# ControlDCMotors.net
KiCad netlist of a schematic drawn in EAGLE
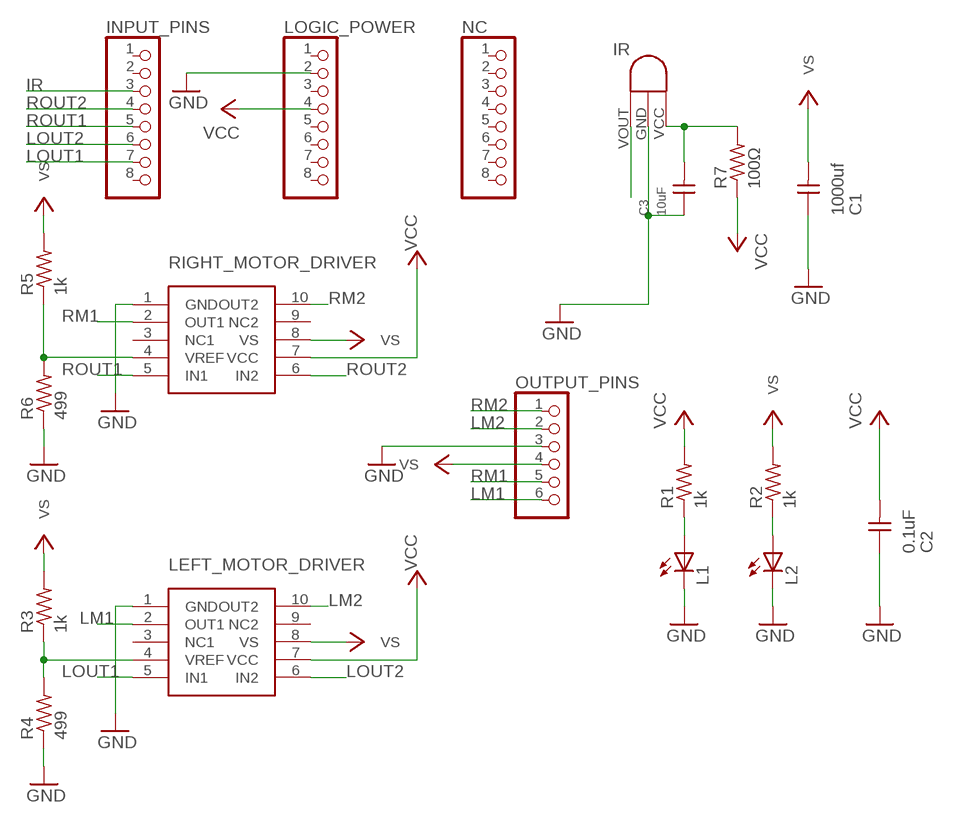
[diagram p0: schematic, sheet 1]

(export (version "E")
  (design (tool "Eeschema 10.0.6"))
  (components
    (comp (ref "C1")
      (value "1000uf")
      (footprint "eagle-import:EPOL5_10.5")
      (libsource (lib "eagle-import") (part "EPOL5_10.5"))
    )
    (comp (ref "C2")
      (value "0.1uF")
      (footprint "eagle-import:1206")
      (libsource (lib "eagle-import") (part "C1206"))
    )
    (comp (ref "C3")
      (value "10uF")
      (footprint "eagle-import:1206")
      (libsource (lib "eagle-import") (part "C1206"))
    )
    (comp (ref "INPUT_PINS")
      (value "PINHD-1X8")
      (footprint "eagle-import:1X08")
      (libsource (lib "eagle-import") (part "PINHD-1X8"))
    )
    (comp (ref "IR_SENSOR")
      (value "IR_SENSOR")
      (footprint "eagle-import:IR_SENSOR")
      (libsource (lib "eagle-import") (part "IR_SENSOR"))
    )
    (comp (ref "L1")
      (value "LED1608")
      (footprint "eagle-import:LED1608")
      (libsource (lib "eagle-import") (part "LED1608"))
    )
    (comp (ref "L2")
      (value "LED1608")
      (footprint "eagle-import:LED1608")
      (libsource (lib "eagle-import") (part "LED1608"))
    )
    (comp (ref "LEFT_MOTOR_DRIVER")
      (value "TA7291P")
      (footprint "eagle-import:HSIP10_P_2.54")
      (libsource (lib "eagle-import") (part "TA7291P"))
    )
    (comp (ref "LOGIC_POWER")
      (value "PINHD-1X8")
      (footprint "eagle-import:1X08")
      (libsource (lib "eagle-import") (part "PINHD-1X8"))
    )
    (comp (ref "NC")
      (value "PINHD-1X8")
      (footprint "eagle-import:1X08")
      (libsource (lib "eagle-import") (part "PINHD-1X8"))
    )
    (comp (ref "OUTPUT_PINS")
      (value "PINHD-1X6")
      (footprint "eagle-import:1X06")
      (libsource (lib "eagle-import") (part "PINHD-1X6"))
    )
    (comp (ref "R1")
      (value "1k")
      (footprint "eagle-import:1206")
      (libsource (lib "eagle-import") (part "R1206"))
    )
    (comp (ref "R2")
      (value "1k")
      (footprint "eagle-import:1206")
      (libsource (lib "eagle-import") (part "R1206"))
    )
    (comp (ref "R3")
      (value "1k")
      (footprint "eagle-import:1206")
      (libsource (lib "eagle-import") (part "R1206"))
    )
    (comp (ref "R4")
      (value "499")
      (footprint "eagle-import:1206")
      (libsource (lib "eagle-import") (part "R1206"))
    )
    (comp (ref "R5")
      (value "1k")
      (footprint "eagle-import:1206")
      (libsource (lib "eagle-import") (part "R1206"))
    )
    (comp (ref "R6")
      (value "499")
      (footprint "eagle-import:1206")
      (libsource (lib "eagle-import") (part "R1206"))
    )
    (comp (ref "R7")
      (value "100Ω")
      (footprint "eagle-import:1206")
      (libsource (lib "eagle-import") (part "R1206"))
    )
    (comp (ref "RIGHT_MOTOR_DRIVER")
      (value "TA7291P")
      (footprint "eagle-import:HSIP10_P_2.54")
      (libsource (lib "eagle-import") (part "TA7291P"))
    )
  )
  (nets
    (net (code "1") (name "/IR") (class "Default")
      (node (ref "INPUT_PINS") (pin "3") (pinfunction "3_3") (pintype "passive"))
      (node (ref "IR_SENSOR") (pin "VOUT") (pinfunction "VOUT_VOUT") (pintype "bidirectional"))
    )
    (net (code "2") (name "/LM1") (class "Default")
      (node (ref "LEFT_MOTOR_DRIVER") (pin "2") (pinfunction "OUT1_2") (pintype "bidirectional"))
      (node (ref "OUTPUT_PINS") (pin "6") (pinfunction "6_6") (pintype "passive"))
    )
    (net (code "3") (name "/LM2") (class "Default")
      (node (ref "LEFT_MOTOR_DRIVER") (pin "10") (pinfunction "OUT2_10") (pintype "bidirectional"))
      (node (ref "OUTPUT_PINS") (pin "2") (pinfunction "2_2") (pintype "passive"))
    )
    (net (code "4") (name "/LOUT1") (class "Default")
      (node (ref "INPUT_PINS") (pin "7") (pinfunction "7_7") (pintype "passive"))
      (node (ref "LEFT_MOTOR_DRIVER") (pin "5") (pinfunction "IN1_5") (pintype "bidirectional"))
    )
    (net (code "5") (name "/LOUT2") (class "Default")
      (node (ref "INPUT_PINS") (pin "6") (pinfunction "6_6") (pintype "passive"))
      (node (ref "LEFT_MOTOR_DRIVER") (pin "6") (pinfunction "IN2_6") (pintype "bidirectional"))
    )
    (net (code "6") (name "/RM1") (class "Default")
      (node (ref "OUTPUT_PINS") (pin "5") (pinfunction "5_5") (pintype "passive"))
      (node (ref "RIGHT_MOTOR_DRIVER") (pin "2") (pinfunction "OUT1_2") (pintype "bidirectional"))
    )
    (net (code "7") (name "/RM2") (class "Default")
      (node (ref "OUTPUT_PINS") (pin "1") (pinfunction "1_1") (pintype "passive"))
      (node (ref "RIGHT_MOTOR_DRIVER") (pin "10") (pinfunction "OUT2_10") (pintype "bidirectional"))
    )
    (net (code "8") (name "/ROUT1") (class "Default")
      (node (ref "INPUT_PINS") (pin "5") (pinfunction "5_5") (pintype "passive"))
      (node (ref "RIGHT_MOTOR_DRIVER") (pin "5") (pinfunction "IN1_5") (pintype "bidirectional"))
    )
    (net (code "9") (name "/ROUT2") (class "Default")
      (node (ref "INPUT_PINS") (pin "4") (pinfunction "4_4") (pintype "passive"))
      (node (ref "RIGHT_MOTOR_DRIVER") (pin "6") (pinfunction "IN2_6") (pintype "bidirectional"))
    )
    (net (code "10") (name "GND") (class "Default")
      (node (ref "C1") (pin "-") (pinfunction "-_-") (pintype "passive"))
      (node (ref "C2") (pin "1") (pinfunction "1_1") (pintype "passive"))
      (node (ref "C3") (pin "1") (pinfunction "1_1") (pintype "passive"))
      (node (ref "IR_SENSOR") (pin "GND") (pinfunction "GND_GND") (pintype "bidirectional"))
      (node (ref "L1") (pin "C") (pinfunction "C_C") (pintype "passive"))
      (node (ref "L2") (pin "C") (pinfunction "C_C") (pintype "passive"))
      (node (ref "LEFT_MOTOR_DRIVER") (pin "1") (pinfunction "GND_1") (pintype "bidirectional"))
      (node (ref "LOGIC_POWER") (pin "2") (pinfunction "2_2") (pintype "passive"))
      (node (ref "OUTPUT_PINS") (pin "3") (pinfunction "3_3") (pintype "passive"))
      (node (ref "R4") (pin "1") (pinfunction "1_1") (pintype "passive"))
      (node (ref "R6") (pin "1") (pinfunction "1_1") (pintype "passive"))
      (node (ref "RIGHT_MOTOR_DRIVER") (pin "1") (pinfunction "GND_1") (pintype "bidirectional"))
    )
    (net (code "11") (name "Net-(C3-Pad2)") (class "Default")
      (node (ref "C3") (pin "2") (pinfunction "2_2") (pintype "passive"))
      (node (ref "IR_SENSOR") (pin "VCC") (pinfunction "VCC_VCC") (pintype "bidirectional"))
      (node (ref "R7") (pin "2") (pinfunction "2_2") (pintype "passive"))
    )
    (net (code "12") (name "Net-(L1-PadA)") (class "Default")
      (node (ref "L1") (pin "A") (pinfunction "A_A") (pintype "passive"))
      (node (ref "R1") (pin "1") (pinfunction "1_1") (pintype "passive"))
    )
    (net (code "13") (name "Net-(L2-PadA)") (class "Default")
      (node (ref "L2") (pin "A") (pinfunction "A_A") (pintype "passive"))
      (node (ref "R2") (pin "1") (pinfunction "1_1") (pintype "passive"))
    )
    (net (code "14") (name "Net-(LEFT_MOTOR_DRIVER-VREF)") (class "Default")
      (node (ref "LEFT_MOTOR_DRIVER") (pin "4") (pinfunction "VREF_4") (pintype "bidirectional"))
      (node (ref "R3") (pin "1") (pinfunction "1_1") (pintype "passive"))
      (node (ref "R4") (pin "2") (pinfunction "2_2") (pintype "passive"))
    )
    (net (code "15") (name "Net-(RIGHT_MOTOR_DRIVER-VREF)") (class "Default")
      (node (ref "R5") (pin "1") (pinfunction "1_1") (pintype "passive"))
      (node (ref "R6") (pin "2") (pinfunction "2_2") (pintype "passive"))
      (node (ref "RIGHT_MOTOR_DRIVER") (pin "4") (pinfunction "VREF_4") (pintype "bidirectional"))
    )
    (net (code "16") (name "VCC") (class "Default")
      (node (ref "C2") (pin "2") (pinfunction "2_2") (pintype "passive"))
      (node (ref "LEFT_MOTOR_DRIVER") (pin "7") (pinfunction "VCC_7") (pintype "bidirectional"))
      (node (ref "LOGIC_POWER") (pin "4") (pinfunction "4_4") (pintype "passive"))
      (node (ref "R1") (pin "2") (pinfunction "2_2") (pintype "passive"))
      (node (ref "R7") (pin "1") (pinfunction "1_1") (pintype "passive"))
      (node (ref "RIGHT_MOTOR_DRIVER") (pin "7") (pinfunction "VCC_7") (pintype "bidirectional"))
    )
    (net (code "17") (name "VS") (class "Default")
      (node (ref "C1") (pin "+") (pinfunction "+_+") (pintype "passive"))
      (node (ref "LEFT_MOTOR_DRIVER") (pin "8") (pinfunction "VS_8") (pintype "bidirectional"))
      (node (ref "OUTPUT_PINS") (pin "4") (pinfunction "4_4") (pintype "passive"))
      (node (ref "R2") (pin "2") (pinfunction "2_2") (pintype "passive"))
      (node (ref "R3") (pin "2") (pinfunction "2_2") (pintype "passive"))
      (node (ref "R5") (pin "2") (pinfunction "2_2") (pintype "passive"))
      (node (ref "RIGHT_MOTOR_DRIVER") (pin "8") (pinfunction "VS_8") (pintype "bidirectional"))
    )
    (net (code "18") (name "unconnected-(INPUT_PINS-Pad1)") (class "Default")
      (node (ref "INPUT_PINS") (pin "1") (pinfunction "1_1") (pintype "passive"))
    )
    (net (code "19") (name "unconnected-(INPUT_PINS-Pad2)") (class "Default")
      (node (ref "INPUT_PINS") (pin "2") (pinfunction "2_2") (pintype "passive"))
    )
    (net (code "20") (name "unconnected-(INPUT_PINS-Pad8)") (class "Default")
      (node (ref "INPUT_PINS") (pin "8") (pinfunction "8_8") (pintype "passive"))
    )
    (net (code "21") (name "unconnected-(LEFT_MOTOR_DRIVER-NC1-Pad3)") (class "Default")
      (node (ref "LEFT_MOTOR_DRIVER") (pin "3") (pinfunction "NC1_3") (pintype "bidirectional"))
    )
    (net (code "22") (name "unconnected-(LEFT_MOTOR_DRIVER-NC2-Pad9)") (class "Default")
      (node (ref "LEFT_MOTOR_DRIVER") (pin "9") (pinfunction "NC2_9") (pintype "bidirectional"))
    )
    (net (code "23") (name "unconnected-(LOGIC_POWER-Pad1)") (class "Default")
      (node (ref "LOGIC_POWER") (pin "1") (pinfunction "1_1") (pintype "passive"))
    )
    (net (code "24") (name "unconnected-(LOGIC_POWER-Pad3)") (class "Default")
      (node (ref "LOGIC_POWER") (pin "3") (pinfunction "3_3") (pintype "passive"))
    )
    (net (code "25") (name "unconnected-(LOGIC_POWER-Pad5)") (class "Default")
      (node (ref "LOGIC_POWER") (pin "5") (pinfunction "5_5") (pintype "passive"))
    )
    (net (code "26") (name "unconnected-(LOGIC_POWER-Pad6)") (class "Default")
      (node (ref "LOGIC_POWER") (pin "6") (pinfunction "6_6") (pintype "passive"))
    )
    (net (code "27") (name "unconnected-(LOGIC_POWER-Pad7)") (class "Default")
      (node (ref "LOGIC_POWER") (pin "7") (pinfunction "7_7") (pintype "passive"))
    )
    (net (code "28") (name "unconnected-(LOGIC_POWER-Pad8)") (class "Default")
      (node (ref "LOGIC_POWER") (pin "8") (pinfunction "8_8") (pintype "passive"))
    )
    (net (code "29") (name "unconnected-(NC-Pad1)") (class "Default")
      (node (ref "NC") (pin "1") (pinfunction "1_1") (pintype "passive"))
    )
    (net (code "30") (name "unconnected-(NC-Pad2)") (class "Default")
      (node (ref "NC") (pin "2") (pinfunction "2_2") (pintype "passive"))
    )
    (net (code "31") (name "unconnected-(NC-Pad3)") (class "Default")
      (node (ref "NC") (pin "3") (pinfunction "3_3") (pintype "passive"))
    )
    (net (code "32") (name "unconnected-(NC-Pad4)") (class "Default")
      (node (ref "NC") (pin "4") (pinfunction "4_4") (pintype "passive"))
    )
    (net (code "33") (name "unconnected-(NC-Pad5)") (class "Default")
      (node (ref "NC") (pin "5") (pinfunction "5_5") (pintype "passive"))
    )
    (net (code "34") (name "unconnected-(NC-Pad6)") (class "Default")
      (node (ref "NC") (pin "6") (pinfunction "6_6") (pintype "passive"))
    )
    (net (code "35") (name "unconnected-(NC-Pad7)") (class "Default")
      (node (ref "NC") (pin "7") (pinfunction "7_7") (pintype "passive"))
    )
    (net (code "36") (name "unconnected-(NC-Pad8)") (class "Default")
      (node (ref "NC") (pin "8") (pinfunction "8_8") (pintype "passive"))
    )
    (net (code "37") (name "unconnected-(RIGHT_MOTOR_DRIVER-NC1-Pad3)") (class "Default")
      (node (ref "RIGHT_MOTOR_DRIVER") (pin "3") (pinfunction "NC1_3") (pintype "bidirectional"))
    )
    (net (code "38") (name "unconnected-(RIGHT_MOTOR_DRIVER-NC2-Pad9)") (class "Default")
      (node (ref "RIGHT_MOTOR_DRIVER") (pin "9") (pinfunction "NC2_9") (pintype "bidirectional"))
    )
  )
)
